# FrontPanel.net
KiCad netlist of a schematic drawn in EAGLE
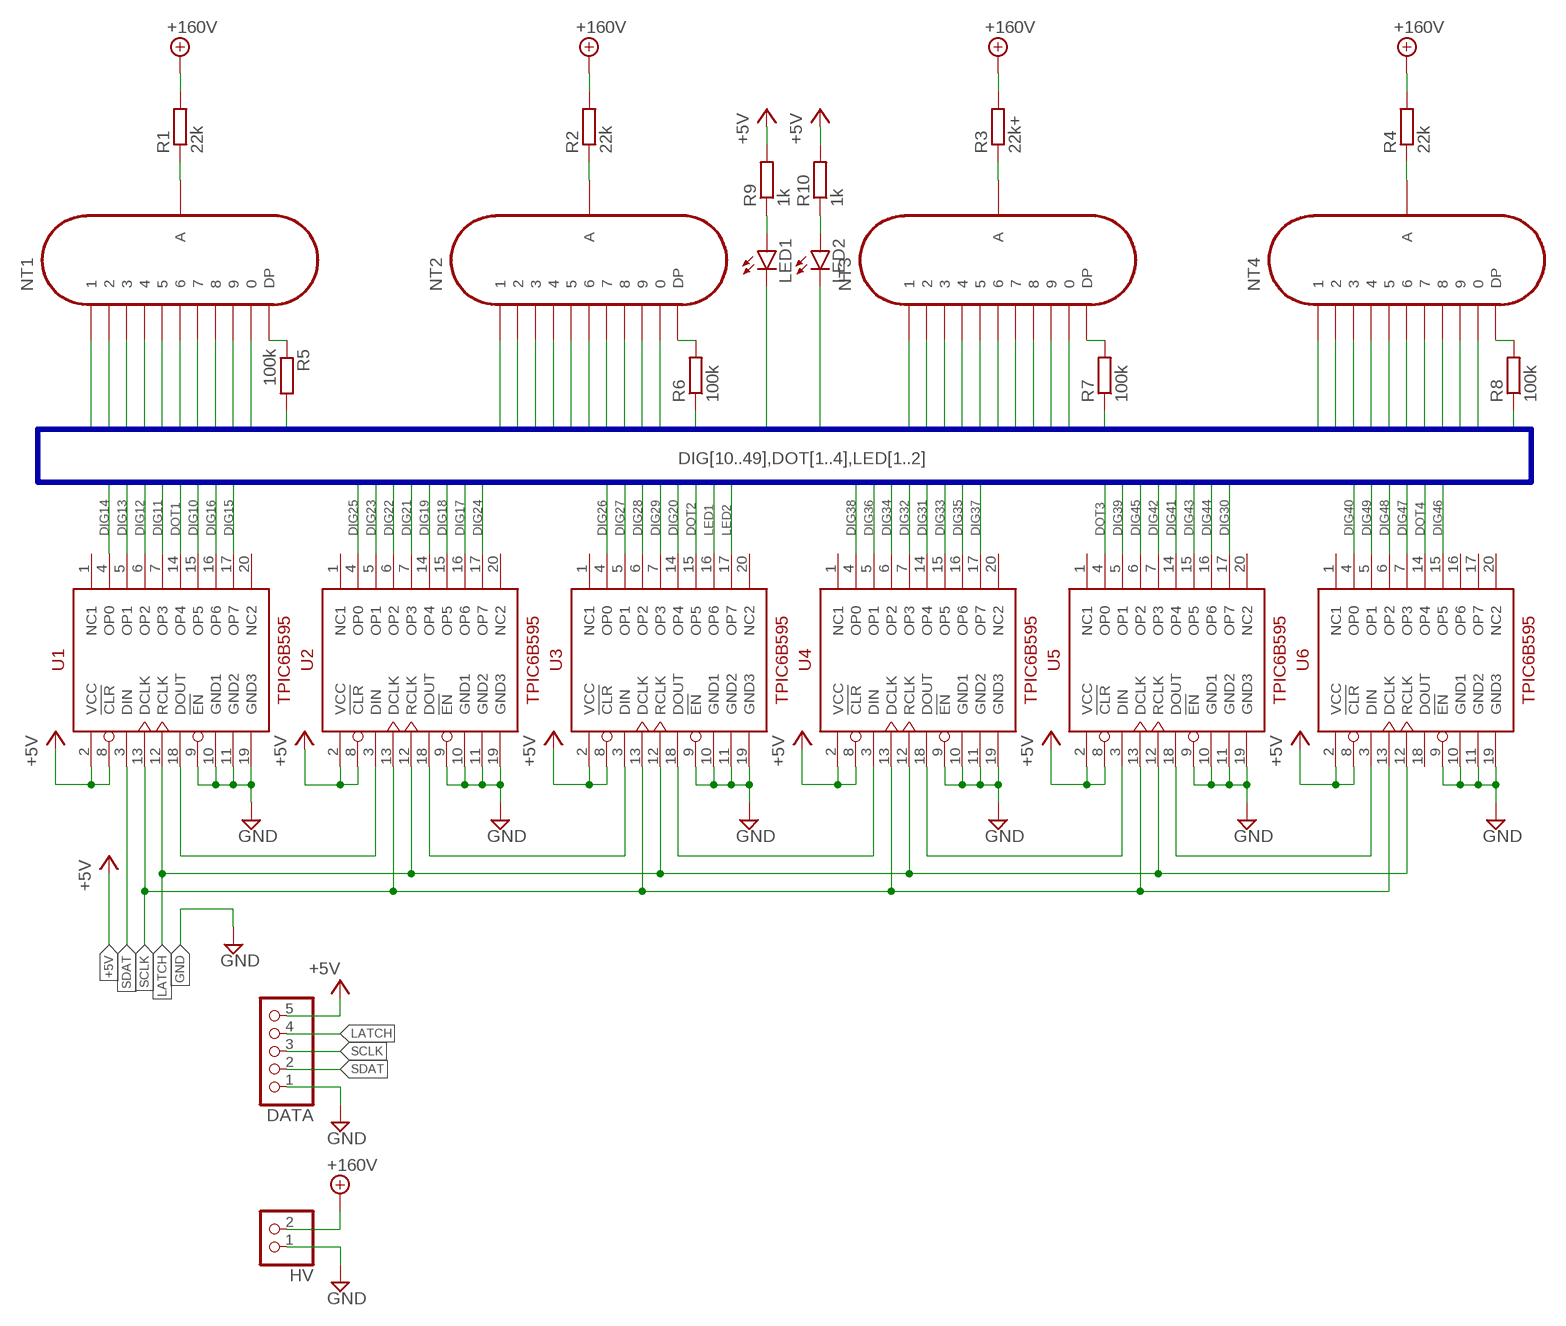
[diagram p0: schematic, sheet 1]

(export (version "E")
  (design (tool "Eeschema 10.0.6"))
  (components
    (comp (ref "DATA")
      (value "PINHD-1X5")
      (footprint "eagle-import:1X05")
      (libsource (lib "eagle-import") (part "PINHD-1X5"))
    )
    (comp (ref "HV")
      (value "PINHD-1X2")
      (footprint "eagle-import:1X02")
      (libsource (lib "eagle-import") (part "PINHD-1X2"))
    )
    (comp (ref "LED1")
      (value "LED5MM")
      (footprint "eagle-import:LED5MM")
      (libsource (lib "eagle-import") (part "LED5MM"))
    )
    (comp (ref "LED2")
      (value "LED5MM")
      (footprint "eagle-import:LED5MM")
      (libsource (lib "eagle-import") (part "LED5MM"))
    )
    (comp (ref "NT1")
      (value "IN-12B")
      (footprint "eagle-import:IN-12")
      (libsource (lib "eagle-import") (part "IN-12B"))
    )
    (comp (ref "NT2")
      (value "IN-12B")
      (footprint "eagle-import:IN-12")
      (libsource (lib "eagle-import") (part "IN-12B"))
    )
    (comp (ref "NT3")
      (value "IN-12B")
      (footprint "eagle-import:IN-12")
      (libsource (lib "eagle-import") (part "IN-12B"))
    )
    (comp (ref "NT4")
      (value "IN-12B")
      (footprint "eagle-import:IN-12")
      (libsource (lib "eagle-import") (part "IN-12B"))
    )
    (comp (ref "R1")
      (value "22k")
      (footprint "eagle-import:0207_10")
      (libsource (lib "eagle-import") (part "R-EU_0207/10"))
    )
    (comp (ref "R2")
      (value "22k")
      (footprint "eagle-import:0207_10")
      (libsource (lib "eagle-import") (part "R-EU_0207/10"))
    )
    (comp (ref "R3")
      (value "22k+")
      (footprint "eagle-import:0207_10")
      (libsource (lib "eagle-import") (part "R-EU_0207/10"))
    )
    (comp (ref "R4")
      (value "22k")
      (footprint "eagle-import:0207_10")
      (libsource (lib "eagle-import") (part "R-EU_0207/10"))
    )
    (comp (ref "R5")
      (value "100k")
      (footprint "eagle-import:0207_10")
      (libsource (lib "eagle-import") (part "R-EU_0207/10"))
    )
    (comp (ref "R6")
      (value "100k")
      (footprint "eagle-import:0207_10")
      (libsource (lib "eagle-import") (part "R-EU_0207/10"))
    )
    (comp (ref "R7")
      (value "100k")
      (footprint "eagle-import:0207_10")
      (libsource (lib "eagle-import") (part "R-EU_0207/10"))
    )
    (comp (ref "R8")
      (value "100k")
      (footprint "eagle-import:0207_10")
      (libsource (lib "eagle-import") (part "R-EU_0207/10"))
    )
    (comp (ref "R9")
      (value "1k")
      (footprint "eagle-import:0207_10")
      (libsource (lib "eagle-import") (part "R-EU_0207/10"))
    )
    (comp (ref "R10")
      (value "1k")
      (footprint "eagle-import:0207_10")
      (libsource (lib "eagle-import") (part "R-EU_0207/10"))
    )
    (comp (ref "U1")
      (value "TPIC6B595N")
      (footprint "eagle-import:PDIP-20")
      (libsource (lib "eagle-import") (part "TPIC6B595N"))
    )
    (comp (ref "U2")
      (value "TPIC6B595N")
      (footprint "eagle-import:PDIP-20")
      (libsource (lib "eagle-import") (part "TPIC6B595N"))
    )
    (comp (ref "U3")
      (value "TPIC6B595N")
      (footprint "eagle-import:PDIP-20")
      (libsource (lib "eagle-import") (part "TPIC6B595N"))
    )
    (comp (ref "U4")
      (value "TPIC6B595N")
      (footprint "eagle-import:PDIP-20")
      (libsource (lib "eagle-import") (part "TPIC6B595N"))
    )
    (comp (ref "U5")
      (value "TPIC6B595N")
      (footprint "eagle-import:PDIP-20")
      (libsource (lib "eagle-import") (part "TPIC6B595N"))
    )
    (comp (ref "U6")
      (value "TPIC6B595N")
      (footprint "eagle-import:PDIP-20")
      (libsource (lib "eagle-import") (part "TPIC6B595N"))
    )
  )
  (nets
    (net (code "1") (name "+5V") (class "Default")
      (node (ref "DATA") (pin "5") (pinfunction "5_5") (pintype "passive"))
      (node (ref "R10") (pin "2") (pinfunction "2_2") (pintype "passive"))
      (node (ref "R9") (pin "2") (pinfunction "2_2") (pintype "passive"))
      (node (ref "U1") (pin "2") (pinfunction "VCC_2") (pintype "power_in"))
      (node (ref "U1") (pin "8") (pinfunction "~{CLR}_8") (pintype "input"))
      (node (ref "U2") (pin "2") (pinfunction "VCC_2") (pintype "power_in"))
      (node (ref "U2") (pin "8") (pinfunction "~{CLR}_8") (pintype "input"))
      (node (ref "U3") (pin "2") (pinfunction "VCC_2") (pintype "power_in"))
      (node (ref "U3") (pin "8") (pinfunction "~{CLR}_8") (pintype "input"))
      (node (ref "U4") (pin "2") (pinfunction "VCC_2") (pintype "power_in"))
      (node (ref "U4") (pin "8") (pinfunction "~{CLR}_8") (pintype "input"))
      (node (ref "U5") (pin "2") (pinfunction "VCC_2") (pintype "power_in"))
      (node (ref "U5") (pin "8") (pinfunction "~{CLR}_8") (pintype "input"))
      (node (ref "U6") (pin "2") (pinfunction "VCC_2") (pintype "power_in"))
      (node (ref "U6") (pin "8") (pinfunction "~{CLR}_8") (pintype "input"))
    )
    (net (code "2") (name "+160V") (class "Default")
      (node (ref "HV") (pin "2") (pinfunction "2_2") (pintype "passive"))
      (node (ref "R1") (pin "2") (pinfunction "2_2") (pintype "passive"))
      (node (ref "R2") (pin "2") (pinfunction "2_2") (pintype "passive"))
      (node (ref "R3") (pin "2") (pinfunction "2_2") (pintype "passive"))
      (node (ref "R4") (pin "2") (pinfunction "2_2") (pintype "passive"))
    )
    (net (code "3") (name "/DIG10") (class "Default")
      (node (ref "NT1") (pin "0") (pinfunction "0_0") (pintype "bidirectional"))
      (node (ref "U1") (pin "15") (pinfunction "OP5_15") (pintype "open_collector"))
    )
    (net (code "4") (name "/DIG11") (class "Default")
      (node (ref "NT1") (pin "1") (pinfunction "1_1") (pintype "bidirectional"))
      (node (ref "U1") (pin "7") (pinfunction "OP3_7") (pintype "open_collector"))
    )
    (net (code "5") (name "/DIG12") (class "Default")
      (node (ref "NT1") (pin "2") (pinfunction "2_2") (pintype "bidirectional"))
      (node (ref "U1") (pin "6") (pinfunction "OP2_6") (pintype "open_collector"))
    )
    (net (code "6") (name "/DIG13") (class "Default")
      (node (ref "NT1") (pin "3") (pinfunction "3_3") (pintype "bidirectional"))
      (node (ref "U1") (pin "5") (pinfunction "OP1_5") (pintype "open_collector"))
    )
    (net (code "7") (name "/DIG14") (class "Default")
      (node (ref "NT1") (pin "4") (pinfunction "4_4") (pintype "bidirectional"))
      (node (ref "U1") (pin "4") (pinfunction "OP0_4") (pintype "open_collector"))
    )
    (net (code "8") (name "/DIG15") (class "Default")
      (node (ref "NT1") (pin "5") (pinfunction "5_5") (pintype "bidirectional"))
      (node (ref "U1") (pin "17") (pinfunction "OP7_17") (pintype "open_collector"))
    )
    (net (code "9") (name "/DIG16") (class "Default")
      (node (ref "NT1") (pin "6") (pinfunction "6_6") (pintype "bidirectional"))
      (node (ref "U1") (pin "16") (pinfunction "OP6_16") (pintype "open_collector"))
    )
    (net (code "10") (name "/DIG17") (class "Default")
      (node (ref "NT1") (pin "7") (pinfunction "7_7") (pintype "bidirectional"))
      (node (ref "U2") (pin "16") (pinfunction "OP6_16") (pintype "open_collector"))
    )
    (net (code "11") (name "/DIG18") (class "Default")
      (node (ref "NT1") (pin "8") (pinfunction "8_8") (pintype "bidirectional"))
      (node (ref "U2") (pin "15") (pinfunction "OP5_15") (pintype "open_collector"))
    )
    (net (code "12") (name "/DIG19") (class "Default")
      (node (ref "NT1") (pin "9") (pinfunction "9_9") (pintype "bidirectional"))
      (node (ref "U2") (pin "14") (pinfunction "OP4_14") (pintype "open_collector"))
    )
    (net (code "13") (name "/DIG20") (class "Default")
      (node (ref "NT2") (pin "0") (pinfunction "0_0") (pintype "bidirectional"))
      (node (ref "U3") (pin "14") (pinfunction "OP4_14") (pintype "open_collector"))
    )
    (net (code "14") (name "/DIG21") (class "Default")
      (node (ref "NT2") (pin "1") (pinfunction "1_1") (pintype "bidirectional"))
      (node (ref "U2") (pin "7") (pinfunction "OP3_7") (pintype "open_collector"))
    )
    (net (code "15") (name "/DIG22") (class "Default")
      (node (ref "NT2") (pin "2") (pinfunction "2_2") (pintype "bidirectional"))
      (node (ref "U2") (pin "6") (pinfunction "OP2_6") (pintype "open_collector"))
    )
    (net (code "16") (name "/DIG23") (class "Default")
      (node (ref "NT2") (pin "3") (pinfunction "3_3") (pintype "bidirectional"))
      (node (ref "U2") (pin "5") (pinfunction "OP1_5") (pintype "open_collector"))
    )
    (net (code "17") (name "/DIG24") (class "Default")
      (node (ref "NT2") (pin "4") (pinfunction "4_4") (pintype "bidirectional"))
      (node (ref "U2") (pin "17") (pinfunction "OP7_17") (pintype "open_collector"))
    )
    (net (code "18") (name "/DIG25") (class "Default")
      (node (ref "NT2") (pin "5") (pinfunction "5_5") (pintype "bidirectional"))
      (node (ref "U2") (pin "4") (pinfunction "OP0_4") (pintype "open_collector"))
    )
    (net (code "19") (name "/DIG26") (class "Default")
      (node (ref "NT2") (pin "6") (pinfunction "6_6") (pintype "bidirectional"))
      (node (ref "U3") (pin "4") (pinfunction "OP0_4") (pintype "open_collector"))
    )
    (net (code "20") (name "/DIG27") (class "Default")
      (node (ref "NT2") (pin "7") (pinfunction "7_7") (pintype "bidirectional"))
      (node (ref "U3") (pin "5") (pinfunction "OP1_5") (pintype "open_collector"))
    )
    (net (code "21") (name "/DIG28") (class "Default")
      (node (ref "NT2") (pin "8") (pinfunction "8_8") (pintype "bidirectional"))
      (node (ref "U3") (pin "6") (pinfunction "OP2_6") (pintype "open_collector"))
    )
    (net (code "22") (name "/DIG29") (class "Default")
      (node (ref "NT2") (pin "9") (pinfunction "9_9") (pintype "bidirectional"))
      (node (ref "U3") (pin "7") (pinfunction "OP3_7") (pintype "open_collector"))
    )
    (net (code "23") (name "/DIG30") (class "Default")
      (node (ref "NT3") (pin "0") (pinfunction "0_0") (pintype "bidirectional"))
      (node (ref "U5") (pin "17") (pinfunction "OP7_17") (pintype "open_collector"))
    )
    (net (code "24") (name "/DIG31") (class "Default")
      (node (ref "NT3") (pin "1") (pinfunction "1_1") (pintype "bidirectional"))
      (node (ref "U4") (pin "14") (pinfunction "OP4_14") (pintype "open_collector"))
    )
    (net (code "25") (name "/DIG32") (class "Default")
      (node (ref "NT3") (pin "2") (pinfunction "2_2") (pintype "bidirectional"))
      (node (ref "U4") (pin "7") (pinfunction "OP3_7") (pintype "open_collector"))
    )
    (net (code "26") (name "/DIG33") (class "Default")
      (node (ref "NT3") (pin "3") (pinfunction "3_3") (pintype "bidirectional"))
      (node (ref "U4") (pin "15") (pinfunction "OP5_15") (pintype "open_collector"))
    )
    (net (code "27") (name "/DIG34") (class "Default")
      (node (ref "NT3") (pin "4") (pinfunction "4_4") (pintype "bidirectional"))
      (node (ref "U4") (pin "6") (pinfunction "OP2_6") (pintype "open_collector"))
    )
    (net (code "28") (name "/DIG35") (class "Default")
      (node (ref "NT3") (pin "5") (pinfunction "5_5") (pintype "bidirectional"))
      (node (ref "U4") (pin "16") (pinfunction "OP6_16") (pintype "open_collector"))
    )
    (net (code "29") (name "/DIG36") (class "Default")
      (node (ref "NT3") (pin "6") (pinfunction "6_6") (pintype "bidirectional"))
      (node (ref "U4") (pin "5") (pinfunction "OP1_5") (pintype "open_collector"))
    )
    (net (code "30") (name "/DIG37") (class "Default")
      (node (ref "NT3") (pin "7") (pinfunction "7_7") (pintype "bidirectional"))
      (node (ref "U4") (pin "17") (pinfunction "OP7_17") (pintype "open_collector"))
    )
    (net (code "31") (name "/DIG38") (class "Default")
      (node (ref "NT3") (pin "8") (pinfunction "8_8") (pintype "bidirectional"))
      (node (ref "U4") (pin "4") (pinfunction "OP0_4") (pintype "open_collector"))
    )
    (net (code "32") (name "/DIG39") (class "Default")
      (node (ref "NT3") (pin "9") (pinfunction "9_9") (pintype "bidirectional"))
      (node (ref "U5") (pin "5") (pinfunction "OP1_5") (pintype "open_collector"))
    )
    (net (code "33") (name "/DIG40") (class "Default")
      (node (ref "NT4") (pin "0") (pinfunction "0_0") (pintype "bidirectional"))
      (node (ref "U6") (pin "4") (pinfunction "OP0_4") (pintype "open_collector"))
    )
    (net (code "34") (name "/DIG41") (class "Default")
      (node (ref "NT4") (pin "1") (pinfunction "1_1") (pintype "bidirectional"))
      (node (ref "U5") (pin "14") (pinfunction "OP4_14") (pintype "open_collector"))
    )
    (net (code "35") (name "/DIG42") (class "Default")
      (node (ref "NT4") (pin "2") (pinfunction "2_2") (pintype "bidirectional"))
      (node (ref "U5") (pin "7") (pinfunction "OP3_7") (pintype "open_collector"))
    )
    (net (code "36") (name "/DIG43") (class "Default")
      (node (ref "NT4") (pin "3") (pinfunction "3_3") (pintype "bidirectional"))
      (node (ref "U5") (pin "15") (pinfunction "OP5_15") (pintype "open_collector"))
    )
    (net (code "37") (name "/DIG44") (class "Default")
      (node (ref "NT4") (pin "4") (pinfunction "4_4") (pintype "bidirectional"))
      (node (ref "U5") (pin "16") (pinfunction "OP6_16") (pintype "open_collector"))
    )
    (net (code "38") (name "/DIG45") (class "Default")
      (node (ref "NT4") (pin "5") (pinfunction "5_5") (pintype "bidirectional"))
      (node (ref "U5") (pin "6") (pinfunction "OP2_6") (pintype "open_collector"))
    )
    (net (code "39") (name "/DIG46") (class "Default")
      (node (ref "NT4") (pin "6") (pinfunction "6_6") (pintype "bidirectional"))
      (node (ref "U6") (pin "15") (pinfunction "OP5_15") (pintype "open_collector"))
    )
    (net (code "40") (name "/DIG47") (class "Default")
      (node (ref "NT4") (pin "7") (pinfunction "7_7") (pintype "bidirectional"))
      (node (ref "U6") (pin "7") (pinfunction "OP3_7") (pintype "open_collector"))
    )
    (net (code "41") (name "/DIG48") (class "Default")
      (node (ref "NT4") (pin "8") (pinfunction "8_8") (pintype "bidirectional"))
      (node (ref "U6") (pin "6") (pinfunction "OP2_6") (pintype "open_collector"))
    )
    (net (code "42") (name "/DIG49") (class "Default")
      (node (ref "NT4") (pin "9") (pinfunction "9_9") (pintype "bidirectional"))
      (node (ref "U6") (pin "5") (pinfunction "OP1_5") (pintype "open_collector"))
    )
    (net (code "43") (name "/DOT1") (class "Default")
      (node (ref "R5") (pin "2") (pinfunction "2_2") (pintype "passive"))
      (node (ref "U1") (pin "14") (pinfunction "OP4_14") (pintype "open_collector"))
    )
    (net (code "44") (name "/DOT2") (class "Default")
      (node (ref "R6") (pin "1") (pinfunction "1_1") (pintype "passive"))
      (node (ref "U3") (pin "15") (pinfunction "OP5_15") (pintype "open_collector"))
    )
    (net (code "45") (name "/DOT3") (class "Default")
      (node (ref "R7") (pin "1") (pinfunction "1_1") (pintype "passive"))
      (node (ref "U5") (pin "4") (pinfunction "OP0_4") (pintype "open_collector"))
    )
    (net (code "46") (name "/DOT4") (class "Default")
      (node (ref "R8") (pin "1") (pinfunction "1_1") (pintype "passive"))
      (node (ref "U6") (pin "14") (pinfunction "OP4_14") (pintype "open_collector"))
    )
    (net (code "47") (name "/LED1") (class "Default")
      (node (ref "LED1") (pin "K") (pinfunction "C_K") (pintype "passive"))
      (node (ref "U3") (pin "16") (pinfunction "OP6_16") (pintype "open_collector"))
    )
    (net (code "48") (name "/LED2") (class "Default")
      (node (ref "LED2") (pin "K") (pinfunction "C_K") (pintype "passive"))
      (node (ref "U3") (pin "17") (pinfunction "OP7_17") (pintype "open_collector"))
    )
    (net (code "50") (name "GND") (class "Default")
      (node (ref "DATA") (pin "1") (pinfunction "1_1") (pintype "passive"))
      (node (ref "HV") (pin "1") (pinfunction "1_1") (pintype "passive"))
      (node (ref "U1") (pin "10") (pinfunction "GND1_10") (pintype "power_in"))
      (node (ref "U1") (pin "11") (pinfunction "GND2_11") (pintype "power_in"))
      (node (ref "U1") (pin "19") (pinfunction "GND3_19") (pintype "power_in"))
      (node (ref "U1") (pin "9") (pinfunction "~{EN}_9") (pintype "input"))
      (node (ref "U2") (pin "10") (pinfunction "GND1_10") (pintype "power_in"))
      (node (ref "U2") (pin "11") (pinfunction "GND2_11") (pintype "power_in"))
      (node (ref "U2") (pin "19") (pinfunction "GND3_19") (pintype "power_in"))
      (node (ref "U2") (pin "9") (pinfunction "~{EN}_9") (pintype "input"))
      (node (ref "U3") (pin "10") (pinfunction "GND1_10") (pintype "power_in"))
      (node (ref "U3") (pin "11") (pinfunction "GND2_11") (pintype "power_in"))
      (node (ref "U3") (pin "19") (pinfunction "GND3_19") (pintype "power_in"))
      (node (ref "U3") (pin "9") (pinfunction "~{EN}_9") (pintype "input"))
      (node (ref "U4") (pin "10") (pinfunction "GND1_10") (pintype "power_in"))
      (node (ref "U4") (pin "11") (pinfunction "GND2_11") (pintype "power_in"))
      (node (ref "U4") (pin "19") (pinfunction "GND3_19") (pintype "power_in"))
      (node (ref "U4") (pin "9") (pinfunction "~{EN}_9") (pintype "input"))
      (node (ref "U5") (pin "10") (pinfunction "GND1_10") (pintype "power_in"))
      (node (ref "U5") (pin "11") (pinfunction "GND2_11") (pintype "power_in"))
      (node (ref "U5") (pin "19") (pinfunction "GND3_19") (pintype "power_in"))
      (node (ref "U5") (pin "9") (pinfunction "~{EN}_9") (pintype "input"))
      (node (ref "U6") (pin "10") (pinfunction "GND1_10") (pintype "power_in"))
      (node (ref "U6") (pin "11") (pinfunction "GND2_11") (pintype "power_in"))
      (node (ref "U6") (pin "19") (pinfunction "GND3_19") (pintype "power_in"))
      (node (ref "U6") (pin "9") (pinfunction "~{EN}_9") (pintype "input"))
    )
    (net (code "51") (name "LATCH") (class "Default")
      (node (ref "DATA") (pin "4") (pinfunction "4_4") (pintype "passive"))
      (node (ref "U1") (pin "12") (pinfunction "RCLK_12") (pintype "input"))
      (node (ref "U2") (pin "12") (pinfunction "RCLK_12") (pintype "input"))
      (node (ref "U3") (pin "12") (pinfunction "RCLK_12") (pintype "input"))
      (node (ref "U4") (pin "12") (pinfunction "RCLK_12") (pintype "input"))
      (node (ref "U5") (pin "12") (pinfunction "RCLK_12") (pintype "input"))
      (node (ref "U6") (pin "12") (pinfunction "RCLK_12") (pintype "input"))
    )
    (net (code "52") (name "Net-(LED1-PadA)") (class "Default")
      (node (ref "LED1") (pin "A") (pinfunction "A_A") (pintype "passive"))
      (node (ref "R9") (pin "1") (pinfunction "1_1") (pintype "passive"))
    )
    (net (code "53") (name "Net-(LED2-PadA)") (class "Default")
      (node (ref "LED2") (pin "A") (pinfunction "A_A") (pintype "passive"))
      (node (ref "R10") (pin "1") (pinfunction "1_1") (pintype "passive"))
    )
    (net (code "54") (name "Net-(NT1-DP)") (class "Default")
      (node (ref "NT1") (pin "LHDP") (pinfunction "DP_LHDP") (pintype "bidirectional"))
      (node (ref "R5") (pin "1") (pinfunction "1_1") (pintype "passive"))
    )
    (net (code "55") (name "Net-(NT1-PadA)") (class "Default")
      (node (ref "NT1") (pin "A") (pinfunction "A_A") (pintype "bidirectional"))
      (node (ref "R1") (pin "1") (pinfunction "1_1") (pintype "passive"))
    )
    (net (code "56") (name "Net-(NT2-DP)") (class "Default")
      (node (ref "NT2") (pin "LHDP") (pinfunction "DP_LHDP") (pintype "bidirectional"))
      (node (ref "R6") (pin "2") (pinfunction "2_2") (pintype "passive"))
    )
    (net (code "57") (name "Net-(NT2-PadA)") (class "Default")
      (node (ref "NT2") (pin "A") (pinfunction "A_A") (pintype "bidirectional"))
      (node (ref "R2") (pin "1") (pinfunction "1_1") (pintype "passive"))
    )
    (net (code "58") (name "Net-(NT3-DP)") (class "Default")
      (node (ref "NT3") (pin "LHDP") (pinfunction "DP_LHDP") (pintype "bidirectional"))
      (node (ref "R7") (pin "2") (pinfunction "2_2") (pintype "passive"))
    )
    (net (code "59") (name "Net-(NT3-PadA)") (class "Default")
      (node (ref "NT3") (pin "A") (pinfunction "A_A") (pintype "bidirectional"))
      (node (ref "R3") (pin "1") (pinfunction "1_1") (pintype "passive"))
    )
    (net (code "60") (name "Net-(NT4-DP)") (class "Default")
      (node (ref "NT4") (pin "LHDP") (pinfunction "DP_LHDP") (pintype "bidirectional"))
      (node (ref "R8") (pin "2") (pinfunction "2_2") (pintype "passive"))
    )
    (net (code "61") (name "Net-(NT4-PadA)") (class "Default")
      (node (ref "NT4") (pin "A") (pinfunction "A_A") (pintype "bidirectional"))
      (node (ref "R4") (pin "1") (pinfunction "1_1") (pintype "passive"))
    )
    (net (code "62") (name "Net-(U1-DOUT)") (class "Default")
      (node (ref "U1") (pin "18") (pinfunction "DOUT_18") (pintype "output"))
      (node (ref "U2") (pin "3") (pinfunction "DIN_3") (pintype "input"))
    )
    (net (code "63") (name "Net-(U2-DOUT)") (class "Default")
      (node (ref "U2") (pin "18") (pinfunction "DOUT_18") (pintype "output"))
      (node (ref "U3") (pin "3") (pinfunction "DIN_3") (pintype "input"))
    )
    (net (code "64") (name "Net-(U3-DOUT)") (class "Default")
      (node (ref "U3") (pin "18") (pinfunction "DOUT_18") (pintype "output"))
      (node (ref "U4") (pin "3") (pinfunction "DIN_3") (pintype "input"))
    )
    (net (code "65") (name "Net-(U4-DOUT)") (class "Default")
      (node (ref "U4") (pin "18") (pinfunction "DOUT_18") (pintype "output"))
      (node (ref "U5") (pin "3") (pinfunction "DIN_3") (pintype "input"))
    )
    (net (code "66") (name "Net-(U5-DOUT)") (class "Default")
      (node (ref "U5") (pin "18") (pinfunction "DOUT_18") (pintype "output"))
      (node (ref "U6") (pin "3") (pinfunction "DIN_3") (pintype "input"))
    )
    (net (code "67") (name "SCLK") (class "Default")
      (node (ref "DATA") (pin "3") (pinfunction "3_3") (pintype "passive"))
      (node (ref "U1") (pin "13") (pinfunction "DCLK_13") (pintype "input"))
      (node (ref "U2") (pin "13") (pinfunction "DCLK_13") (pintype "input"))
      (node (ref "U3") (pin "13") (pinfunction "DCLK_13") (pintype "input"))
      (node (ref "U4") (pin "13") (pinfunction "DCLK_13") (pintype "input"))
      (node (ref "U5") (pin "13") (pinfunction "DCLK_13") (pintype "input"))
      (node (ref "U6") (pin "13") (pinfunction "DCLK_13") (pintype "input"))
    )
    (net (code "68") (name "SDAT") (class "Default")
      (node (ref "DATA") (pin "2") (pinfunction "2_2") (pintype "passive"))
      (node (ref "U1") (pin "3") (pinfunction "DIN_3") (pintype "input"))
    )
    (net (code "69") (name "unconnected-(U1-NC1-Pad1)") (class "Default")
      (node (ref "U1") (pin "1") (pinfunction "NC1_1") (pintype "no_connect"))
    )
    (net (code "70") (name "unconnected-(U1-NC2-Pad20)") (class "Default")
      (node (ref "U1") (pin "20") (pinfunction "NC2_20") (pintype "no_connect"))
    )
    (net (code "71") (name "unconnected-(U2-NC1-Pad1)") (class "Default")
      (node (ref "U2") (pin "1") (pinfunction "NC1_1") (pintype "no_connect"))
    )
    (net (code "72") (name "unconnected-(U2-NC2-Pad20)") (class "Default")
      (node (ref "U2") (pin "20") (pinfunction "NC2_20") (pintype "no_connect"))
    )
    (net (code "73") (name "unconnected-(U3-NC1-Pad1)") (class "Default")
      (node (ref "U3") (pin "1") (pinfunction "NC1_1") (pintype "no_connect"))
    )
    (net (code "74") (name "unconnected-(U3-NC2-Pad20)") (class "Default")
      (node (ref "U3") (pin "20") (pinfunction "NC2_20") (pintype "no_connect"))
    )
    (net (code "75") (name "unconnected-(U4-NC1-Pad1)") (class "Default")
      (node (ref "U4") (pin "1") (pinfunction "NC1_1") (pintype "no_connect"))
    )
    (net (code "76") (name "unconnected-(U4-NC2-Pad20)") (class "Default")
      (node (ref "U4") (pin "20") (pinfunction "NC2_20") (pintype "no_connect"))
    )
    (net (code "77") (name "unconnected-(U5-NC1-Pad1)") (class "Default")
      (node (ref "U5") (pin "1") (pinfunction "NC1_1") (pintype "no_connect"))
    )
    (net (code "78") (name "unconnected-(U5-NC2-Pad20)") (class "Default")
      (node (ref "U5") (pin "20") (pinfunction "NC2_20") (pintype "no_connect"))
    )
    (net (code "79") (name "unconnected-(U6-DOUT-Pad18)") (class "Default")
      (node (ref "U6") (pin "18") (pinfunction "DOUT_18") (pintype "output"))
    )
    (net (code "80") (name "unconnected-(U6-NC1-Pad1)") (class "Default")
      (node (ref "U6") (pin "1") (pinfunction "NC1_1") (pintype "no_connect"))
    )
    (net (code "81") (name "unconnected-(U6-NC2-Pad20)") (class "Default")
      (node (ref "U6") (pin "20") (pinfunction "NC2_20") (pintype "no_connect"))
    )
    (net (code "82") (name "unconnected-(U6-OP6-Pad16)") (class "Default")
      (node (ref "U6") (pin "16") (pinfunction "OP6_16") (pintype "open_collector"))
    )
    (net (code "83") (name "unconnected-(U6-OP7-Pad17)") (class "Default")
      (node (ref "U6") (pin "17") (pinfunction "OP7_17") (pintype "open_collector"))
    )
  )
)
